# UMC.net
KiCad netlist of a schematic drawn in EAGLE
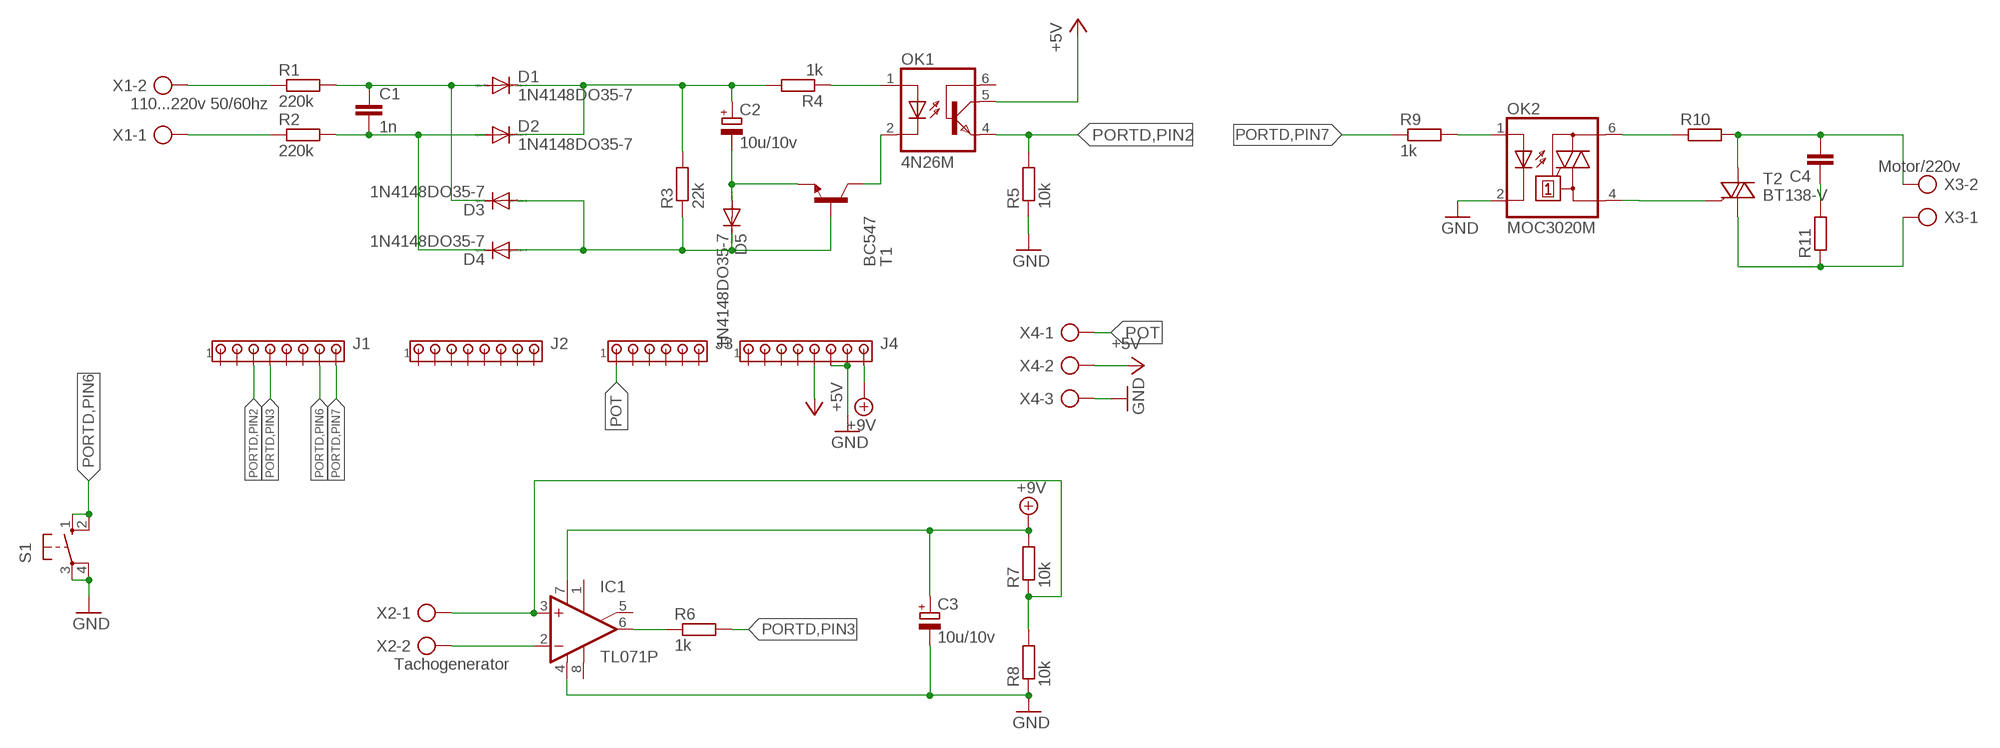
[diagram p0: schematic, sheet 1]

(export (version "E")
  (design (tool "Eeschema 10.0.6"))
  (components
    (comp (ref "C1")
      (value "1n")
      (footprint "eagle-import:C5B2.5")
      (libsource (lib "eagle-import") (part "C5/2.5"))
    )
    (comp (ref "C2")
      (value "10u/10v")
      (footprint "eagle-import:E2,5-5")
      (libsource (lib "eagle-import") (part "CPOL-EUE2.5-5"))
    )
    (comp (ref "C3")
      (value "10u/10v")
      (footprint "eagle-import:E2,5-5")
      (libsource (lib "eagle-import") (part "CPOL-EUE2.5-5"))
    )
    (comp (ref "C4")
      (value "C15/7")
      (footprint "eagle-import:C15B7")
      (libsource (lib "eagle-import") (part "C15/7"))
    )
    (comp (ref "D1")
      (value "1N4148DO35-7")
      (footprint "eagle-import:DO35-7")
      (libsource (lib "eagle-import") (part "1N4148DO35-7"))
    )
    (comp (ref "D2")
      (value "1N4148DO35-7")
      (footprint "eagle-import:DO35-7")
      (libsource (lib "eagle-import") (part "1N4148DO35-7"))
    )
    (comp (ref "D3")
      (value "1N4148DO35-7")
      (footprint "eagle-import:DO35-7")
      (libsource (lib "eagle-import") (part "1N4148DO35-7"))
    )
    (comp (ref "D4")
      (value "1N4148DO35-7")
      (footprint "eagle-import:DO35-7")
      (libsource (lib "eagle-import") (part "1N4148DO35-7"))
    )
    (comp (ref "D5")
      (value "1N4148DO35-7")
      (footprint "eagle-import:DO35-7")
      (libsource (lib "eagle-import") (part "1N4148DO35-7"))
    )
    (comp (ref "IC1")
      (value "TL071P")
      (footprint "eagle-import:DIL08")
      (libsource (lib "eagle-import") (part "TL071P"))
    )
    (comp (ref "J1")
      (value "MTA08-100")
      (footprint "eagle-import:10X08MTA")
      (libsource (lib "eagle-import") (part "MTA08-100"))
    )
    (comp (ref "J2")
      (value "MTA08-100")
      (footprint "eagle-import:10X08MTA")
      (libsource (lib "eagle-import") (part "MTA08-100"))
    )
    (comp (ref "J3")
      (value "MTA06-100")
      (footprint "eagle-import:10X06MTA")
      (libsource (lib "eagle-import") (part "MTA06-100"))
    )
    (comp (ref "J4")
      (value "MTA08-100")
      (footprint "eagle-import:10X08MTA")
      (libsource (lib "eagle-import") (part "MTA08-100"))
    )
    (comp (ref "OK1")
      (value "4N26M")
      (footprint "eagle-import:DIL06")
      (fields (field (name "MPN") "4N26-M"))
      (libsource (lib "eagle-import") (part "4N?M26"))
    )
    (comp (ref "OK2")
      (value "MOC3020M")
      (footprint "eagle-import:DIL06")
      (fields (field (name "MF") "FAIRCHILD SEMICONDUCTOR") (field (name "MPN") "MOC3020-M"))
      (libsource (lib "eagle-import") (part "MOC30M20"))
    )
    (comp (ref "R1")
      (value "220k")
      (footprint "eagle-import:0207_7")
      (libsource (lib "eagle-import") (part "resistor_348_R-EU_0207/7"))
    )
    (comp (ref "R2")
      (value "220k")
      (footprint "eagle-import:0207_7")
      (libsource (lib "eagle-import") (part "resistor_348_R-EU_0207/7"))
    )
    (comp (ref "R3")
      (value "22k")
      (footprint "eagle-import:0207_7")
      (libsource (lib "eagle-import") (part "resistor_348_R-EU_0207/7"))
    )
    (comp (ref "R4")
      (value "1k")
      (footprint "eagle-import:0207_7")
      (libsource (lib "eagle-import") (part "resistor_348_R-EU_0207/7"))
    )
    (comp (ref "R5")
      (value "10k")
      (footprint "eagle-import:0207_7")
      (libsource (lib "eagle-import") (part "resistor_348_R-EU_0207/7"))
    )
    (comp (ref "R6")
      (value "1k")
      (footprint "eagle-import:0207_7")
      (libsource (lib "eagle-import") (part "resistor_348_R-EU_0207/7"))
    )
    (comp (ref "R7")
      (value "10k")
      (footprint "eagle-import:0207_7")
      (libsource (lib "eagle-import") (part "resistor_348_R-EU_0207/7"))
    )
    (comp (ref "R8")
      (value "10k")
      (footprint "eagle-import:0207_7")
      (libsource (lib "eagle-import") (part "resistor_348_R-EU_0207/7"))
    )
    (comp (ref "R9")
      (value "1k")
      (footprint "eagle-import:0207_7")
      (libsource (lib "eagle-import") (part "resistor_348_R-EU_0207/7"))
    )
    (comp (ref "R10")
      (value "R-EU_0207/7")
      (footprint "eagle-import:0207_7")
      (libsource (lib "eagle-import") (part "R-EU_0207/7"))
    )
    (comp (ref "R11")
      (value "R-EU_0411/12")
      (footprint "eagle-import:0411_12")
      (libsource (lib "eagle-import") (part "R-EU_0411/12"))
    )
    (comp (ref "S1")
      (value "10-XX")
      (footprint "eagle-import:B3F-10XX")
      (fields (field (name "MPN") "B3F-1000"))
      (libsource (lib "eagle-import") (part "10-XX"))
    )
    (comp (ref "T1")
      (value "BC547")
      (footprint "eagle-import:TO92")
      (libsource (lib "eagle-import") (part "BC547"))
    )
    (comp (ref "T2")
      (value "BT138-V")
      (footprint "eagle-import:TO220BV")
      (libsource (lib "eagle-import") (part "BT138-V"))
    )
    (comp (ref "X1")
      (value "110...220v 50/60hz")
      (footprint "eagle-import:AK500_2")
      (libsource (lib "eagle-import") (part "AK500/2"))
    )
    (comp (ref "X2")
      (value "Tachogenerator")
      (footprint "eagle-import:AK500_2")
      (libsource (lib "eagle-import") (part "AK500/2"))
    )
    (comp (ref "X3")
      (value "Motor/220v")
      (footprint "eagle-import:AK500_2")
      (libsource (lib "eagle-import") (part "AK500/2"))
    )
    (comp (ref "X4")
      (value "AK500/3")
      (footprint "eagle-import:AK500_3")
      (libsource (lib "eagle-import") (part "AK500/3"))
    )
  )
  (nets
    (net (code "1") (name "+5V") (class "Default")
      (node (ref "J4") (pin "5") (pinfunction "5_5") (pintype "passive"))
      (node (ref "OK1") (pin "5") (pinfunction "COL_5") (pintype "passive"))
      (node (ref "X4") (pin "2") (pinfunction "KL_2") (pintype "passive"))
    )
    (net (code "2") (name "+9V") (class "Default")
      (node (ref "C3") (pin "+") (pinfunction "+_+") (pintype "passive"))
      (node (ref "IC1") (pin "7") (pinfunction "V+_7") (pintype "power_in"))
      (node (ref "J4") (pin "8") (pinfunction "8_8") (pintype "passive"))
      (node (ref "R7") (pin "2") (pinfunction "2_2") (pintype "passive"))
    )
    (net (code "3") (name "GND") (class "Default")
      (node (ref "C3") (pin "-") (pinfunction "-_-") (pintype "passive"))
      (node (ref "IC1") (pin "4") (pinfunction "V-_4") (pintype "power_in"))
      (node (ref "J4") (pin "6") (pinfunction "6_6") (pintype "passive"))
      (node (ref "J4") (pin "7") (pinfunction "7_7") (pintype "passive"))
      (node (ref "OK2") (pin "2") (pinfunction "C_2") (pintype "passive"))
      (node (ref "R5") (pin "1") (pinfunction "1_1") (pintype "passive"))
      (node (ref "R8") (pin "1") (pinfunction "1_1") (pintype "passive"))
      (node (ref "S1") (pin "3") (pinfunction "P_3") (pintype "passive"))
      (node (ref "S1") (pin "4") (pinfunction "P1_4") (pintype "passive"))
      (node (ref "X4") (pin "3") (pinfunction "KL_3") (pintype "passive"))
    )
    (net (code "4") (name "Net-(C1-Pad1)") (class "Default")
      (node (ref "C1") (pin "1") (pinfunction "1_1") (pintype "passive"))
      (node (ref "D1") (pin "A") (pinfunction "A_A") (pintype "passive"))
      (node (ref "D3") (pin "C") (pinfunction "C_C") (pintype "passive"))
      (node (ref "R1") (pin "2") (pinfunction "2_2") (pintype "passive"))
    )
    (net (code "5") (name "Net-(C1-Pad2)") (class "Default")
      (node (ref "C1") (pin "2") (pinfunction "2_2") (pintype "passive"))
      (node (ref "D2") (pin "A") (pinfunction "A_A") (pintype "passive"))
      (node (ref "D4") (pin "C") (pinfunction "C_C") (pintype "passive"))
      (node (ref "R2") (pin "2") (pinfunction "2_2") (pintype "passive"))
    )
    (net (code "6") (name "Net-(C2-Pad+)") (class "Default")
      (node (ref "C2") (pin "+") (pinfunction "+_+") (pintype "passive"))
      (node (ref "D1") (pin "C") (pinfunction "C_C") (pintype "passive"))
      (node (ref "D2") (pin "C") (pinfunction "C_C") (pintype "passive"))
      (node (ref "R3") (pin "2") (pinfunction "2_2") (pintype "passive"))
      (node (ref "R4") (pin "2") (pinfunction "2_2") (pintype "passive"))
    )
    (net (code "7") (name "Net-(C4-Pad1)") (class "Default")
      (node (ref "C4") (pin "1") (pinfunction "1_1") (pintype "passive"))
      (node (ref "R11") (pin "2") (pinfunction "2_2") (pintype "passive"))
    )
    (net (code "8") (name "Net-(IC1-+IN)") (class "Default")
      (node (ref "IC1") (pin "3") (pinfunction "+IN_3") (pintype "input"))
      (node (ref "R7") (pin "1") (pinfunction "1_1") (pintype "passive"))
      (node (ref "R8") (pin "2") (pinfunction "2_2") (pintype "passive"))
      (node (ref "X2") (pin "1") (pinfunction "KL_1") (pintype "passive"))
    )
    (net (code "9") (name "Net-(IC1--IN)") (class "Default")
      (node (ref "IC1") (pin "2") (pinfunction "-IN_2") (pintype "input"))
      (node (ref "X2") (pin "2") (pinfunction "KL_2") (pintype "passive"))
    )
    (net (code "10") (name "Net-(IC1-OUT)") (class "Default")
      (node (ref "IC1") (pin "6") (pinfunction "OUT_6") (pintype "output"))
      (node (ref "R6") (pin "1") (pinfunction "1_1") (pintype "passive"))
    )
    (net (code "11") (name "Net-(OK1-A)") (class "Default")
      (node (ref "OK1") (pin "1") (pinfunction "A_1") (pintype "passive"))
      (node (ref "R4") (pin "1") (pinfunction "1_1") (pintype "passive"))
    )
    (net (code "12") (name "Net-(OK1-C)") (class "Default")
      (node (ref "OK1") (pin "2") (pinfunction "C_2") (pintype "passive"))
      (node (ref "T1") (pin "3") (pinfunction "C_3") (pintype "passive"))
    )
    (net (code "13") (name "Net-(OK2-A)") (class "Default")
      (node (ref "OK2") (pin "1") (pinfunction "A_1") (pintype "passive"))
      (node (ref "R9") (pin "2") (pinfunction "2_2") (pintype "passive"))
    )
    (net (code "14") (name "Net-(OK2-A1)") (class "Default")
      (node (ref "OK2") (pin "4") (pinfunction "A1_4") (pintype "passive"))
      (node (ref "T2") (pin "G") (pinfunction "G_G") (pintype "passive"))
    )
    (net (code "15") (name "Net-(OK2-A2)") (class "Default")
      (node (ref "OK2") (pin "6") (pinfunction "A2_6") (pintype "passive"))
      (node (ref "R10") (pin "1") (pinfunction "1_1") (pintype "passive"))
    )
    (net (code "16") (name "Net-(T1-B)") (class "Default")
      (node (ref "D3") (pin "A") (pinfunction "A_A") (pintype "passive"))
      (node (ref "D4") (pin "A") (pinfunction "A_A") (pintype "passive"))
      (node (ref "D5") (pin "C") (pinfunction "C_C") (pintype "passive"))
      (node (ref "R3") (pin "1") (pinfunction "1_1") (pintype "passive"))
      (node (ref "T1") (pin "2") (pinfunction "B_2") (pintype "passive"))
    )
    (net (code "17") (name "Net-(T1-E)") (class "Default")
      (node (ref "C2") (pin "-") (pinfunction "-_-") (pintype "passive"))
      (node (ref "D5") (pin "A") (pinfunction "A_A") (pintype "passive"))
      (node (ref "T1") (pin "1") (pinfunction "E_1") (pintype "passive"))
    )
    (net (code "18") (name "Net-(T2-A1)") (class "Default")
      (node (ref "R11") (pin "1") (pinfunction "1_1") (pintype "passive"))
      (node (ref "T2") (pin "T1") (pinfunction "A1_T1") (pintype "passive"))
      (node (ref "X3") (pin "1") (pinfunction "KL_1") (pintype "passive"))
    )
    (net (code "19") (name "Net-(T2-A2)") (class "Default")
      (node (ref "C4") (pin "2") (pinfunction "2_2") (pintype "passive"))
      (node (ref "R10") (pin "2") (pinfunction "2_2") (pintype "passive"))
      (node (ref "T2") (pin "T2") (pinfunction "A2_T2") (pintype "passive"))
      (node (ref "X3") (pin "2") (pinfunction "KL_2") (pintype "passive"))
    )
    (net (code "20") (name "Net-(X1A-KL)") (class "Default")
      (node (ref "R2") (pin "1") (pinfunction "1_1") (pintype "passive"))
      (node (ref "X1") (pin "1") (pinfunction "KL_1") (pintype "passive"))
    )
    (net (code "21") (name "Net-(X1B-KL)") (class "Default")
      (node (ref "R1") (pin "1") (pinfunction "1_1") (pintype "passive"))
      (node (ref "X1") (pin "2") (pinfunction "KL_2") (pintype "passive"))
    )
    (net (code "22") (name "PORTD,PIN2") (class "Default")
      (node (ref "J1") (pin "3") (pinfunction "3_3") (pintype "passive"))
      (node (ref "OK1") (pin "4") (pinfunction "EMI_4") (pintype "passive"))
      (node (ref "R5") (pin "2") (pinfunction "2_2") (pintype "passive"))
    )
    (net (code "23") (name "PORTD,PIN3") (class "Default")
      (node (ref "J1") (pin "4") (pinfunction "4_4") (pintype "passive"))
      (node (ref "R6") (pin "2") (pinfunction "2_2") (pintype "passive"))
    )
    (net (code "24") (name "PORTD,PIN6") (class "Default")
      (node (ref "J1") (pin "7") (pinfunction "7_7") (pintype "passive"))
      (node (ref "S1") (pin "1") (pinfunction "S_1") (pintype "passive"))
      (node (ref "S1") (pin "2") (pinfunction "S1_2") (pintype "passive"))
    )
    (net (code "25") (name "PORTD,PIN7") (class "Default")
      (node (ref "J1") (pin "8") (pinfunction "8_8") (pintype "passive"))
      (node (ref "R9") (pin "1") (pinfunction "1_1") (pintype "passive"))
    )
    (net (code "26") (name "POT") (class "Default")
      (node (ref "J3") (pin "1") (pinfunction "1_1") (pintype "passive"))
      (node (ref "X4") (pin "1") (pinfunction "KL_1") (pintype "passive"))
    )
    (net (code "27") (name "unconnected-(IC1-ON1-Pad1)") (class "Default")
      (node (ref "IC1") (pin "1") (pinfunction "ON1_1") (pintype "passive"))
    )
    (net (code "28") (name "unconnected-(IC1-ON2-Pad5)") (class "Default")
      (node (ref "IC1") (pin "5") (pinfunction "ON2_5") (pintype "passive"))
    )
    (net (code "29") (name "unconnected-(IC1-OPT-Pad8)") (class "Default")
      (node (ref "IC1") (pin "8") (pinfunction "OPT_8") (pintype "passive"))
    )
    (net (code "30") (name "unconnected-(J1-Pad1)") (class "Default")
      (node (ref "J1") (pin "1") (pinfunction "1_1") (pintype "passive"))
    )
    (net (code "31") (name "unconnected-(J1-Pad2)") (class "Default")
      (node (ref "J1") (pin "2") (pinfunction "2_2") (pintype "passive"))
    )
    (net (code "32") (name "unconnected-(J1-Pad5)") (class "Default")
      (node (ref "J1") (pin "5") (pinfunction "5_5") (pintype "passive"))
    )
    (net (code "33") (name "unconnected-(J1-Pad6)") (class "Default")
      (node (ref "J1") (pin "6") (pinfunction "6_6") (pintype "passive"))
    )
    (net (code "34") (name "unconnected-(J2-Pad1)") (class "Default")
      (node (ref "J2") (pin "1") (pinfunction "1_1") (pintype "passive"))
    )
    (net (code "35") (name "unconnected-(J2-Pad2)") (class "Default")
      (node (ref "J2") (pin "2") (pinfunction "2_2") (pintype "passive"))
    )
    (net (code "36") (name "unconnected-(J2-Pad3)") (class "Default")
      (node (ref "J2") (pin "3") (pinfunction "3_3") (pintype "passive"))
    )
    (net (code "37") (name "unconnected-(J2-Pad4)") (class "Default")
      (node (ref "J2") (pin "4") (pinfunction "4_4") (pintype "passive"))
    )
    (net (code "38") (name "unconnected-(J2-Pad5)") (class "Default")
      (node (ref "J2") (pin "5") (pinfunction "5_5") (pintype "passive"))
    )
    (net (code "39") (name "unconnected-(J2-Pad6)") (class "Default")
      (node (ref "J2") (pin "6") (pinfunction "6_6") (pintype "passive"))
    )
    (net (code "40") (name "unconnected-(J2-Pad7)") (class "Default")
      (node (ref "J2") (pin "7") (pinfunction "7_7") (pintype "passive"))
    )
    (net (code "41") (name "unconnected-(J2-Pad8)") (class "Default")
      (node (ref "J2") (pin "8") (pinfunction "8_8") (pintype "passive"))
    )
    (net (code "42") (name "unconnected-(J3-Pad2)") (class "Default")
      (node (ref "J3") (pin "2") (pinfunction "2_2") (pintype "passive"))
    )
    (net (code "43") (name "unconnected-(J3-Pad3)") (class "Default")
      (node (ref "J3") (pin "3") (pinfunction "3_3") (pintype "passive"))
    )
    (net (code "44") (name "unconnected-(J3-Pad4)") (class "Default")
      (node (ref "J3") (pin "4") (pinfunction "4_4") (pintype "passive"))
    )
    (net (code "45") (name "unconnected-(J3-Pad5)") (class "Default")
      (node (ref "J3") (pin "5") (pinfunction "5_5") (pintype "passive"))
    )
    (net (code "46") (name "unconnected-(J3-Pad6)") (class "Default")
      (node (ref "J3") (pin "6") (pinfunction "6_6") (pintype "passive"))
    )
    (net (code "47") (name "unconnected-(J4-Pad1)") (class "Default")
      (node (ref "J4") (pin "1") (pinfunction "1_1") (pintype "passive"))
    )
    (net (code "48") (name "unconnected-(J4-Pad2)") (class "Default")
      (node (ref "J4") (pin "2") (pinfunction "2_2") (pintype "passive"))
    )
    (net (code "49") (name "unconnected-(J4-Pad3)") (class "Default")
      (node (ref "J4") (pin "3") (pinfunction "3_3") (pintype "passive"))
    )
    (net (code "50") (name "unconnected-(J4-Pad4)") (class "Default")
      (node (ref "J4") (pin "4") (pinfunction "4_4") (pintype "passive"))
    )
    (net (code "51") (name "unconnected-(OK1-BAS-Pad6)") (class "Default")
      (node (ref "OK1") (pin "6") (pinfunction "BAS_6") (pintype "passive"))
    )
  )
)
